# 3_sensors.net
KiCad netlist of a schematic drawn in Altium Designer
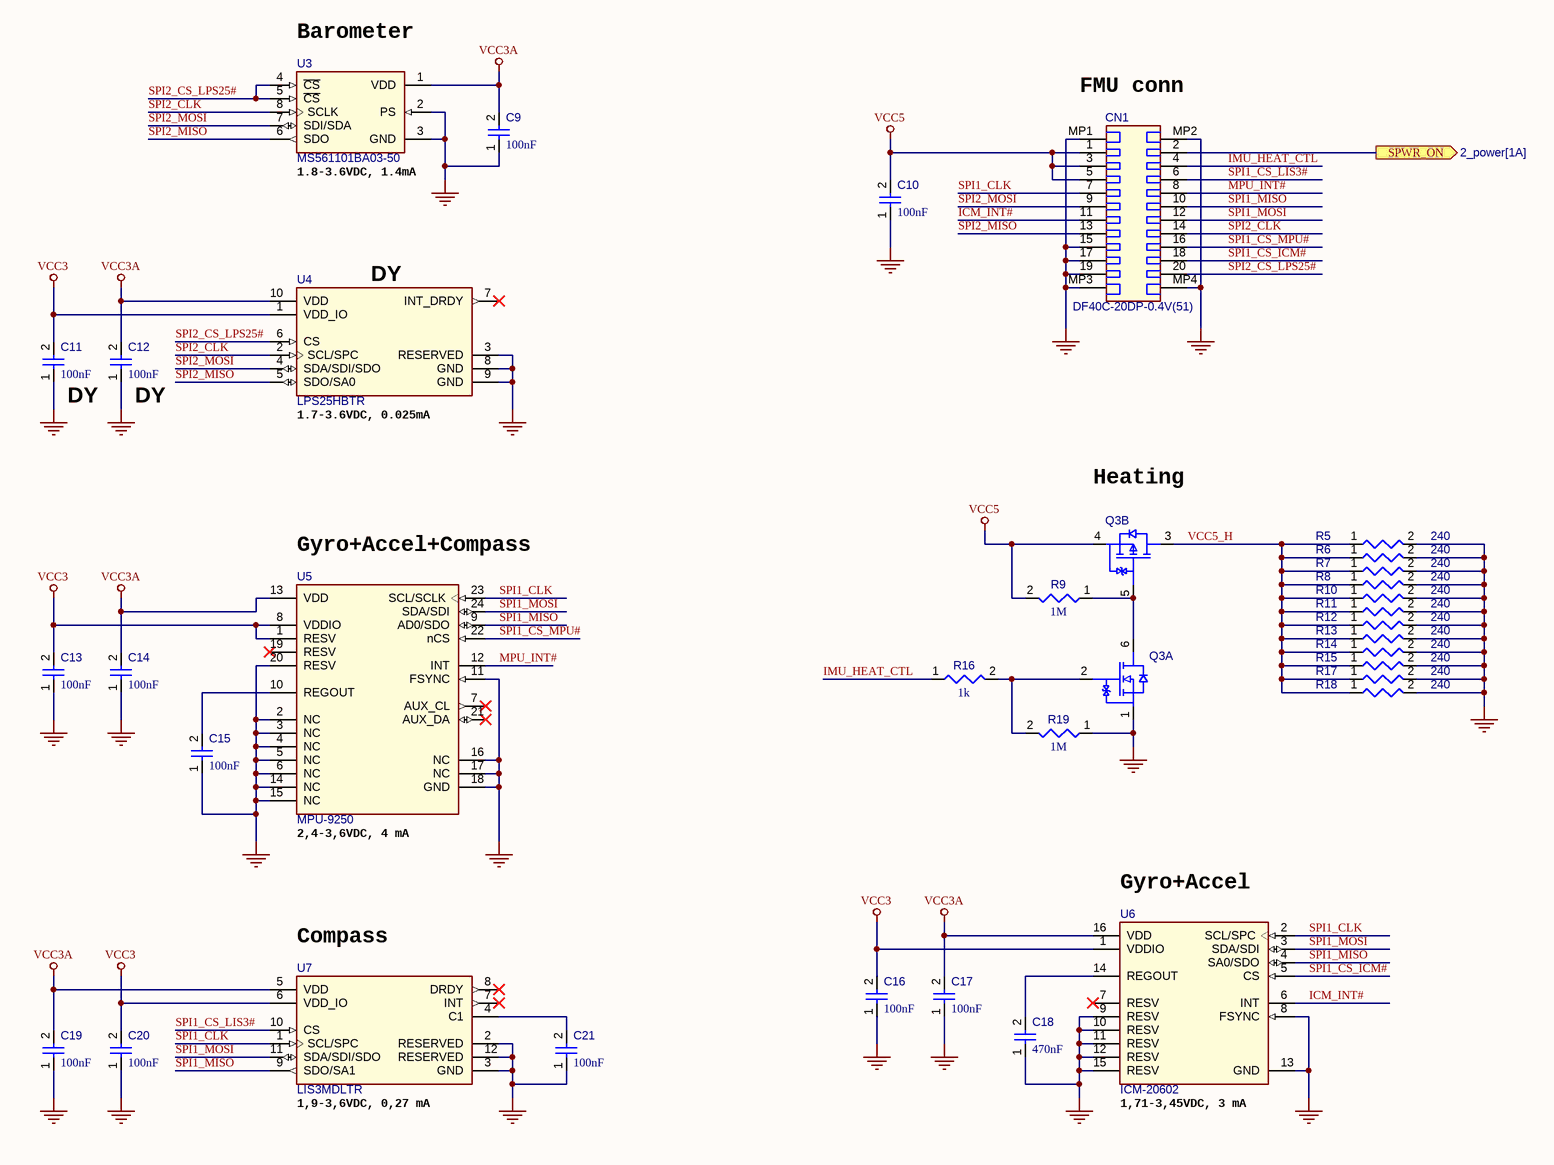
[diagram p0: 3_sensors.SchDoc]

(export (version "E")
  (design (tool "Eeschema 10.0.6"))
  (components
    (comp (ref "C9")
      (value "100nF")
      (footprint "CAPC0402(1005)60_L")
      (description "Chip Capacitor, 100nF +/-20%, 10V, 0402, Thickness 0.6 mm")
      (fields (field (name "TOLERANCE") "20%") (field (name "Comment") "Capacitor 100nF +/-20% 10V 0402"))
      (libsource (lib "SKA- Automa玢o de Engenharias") (part "CAP-NP-2"))
    )
    (comp (ref "C10")
      (value "100nF")
      (footprint "CAPC0402(1005)60_L")
      (description "Chip Capacitor, 100nF +/-20%, 10V, 0402, Thickness 0.6 mm")
      (fields (field (name "TOLERANCE") "20%") (field (name "Comment") "Capacitor 100nF +/-20% 10V 0402"))
      (libsource (lib "SKA- Automa玢o de Engenharias") (part "CAP-NP-2"))
    )
    (comp (ref "C11")
      (value "100nF")
      (footprint "CAPC0402(1005)60_L")
      (description "Chip Capacitor, 100nF +/-20%, 10V, 0402, Thickness 0.6 mm")
      (fields (field (name "TOLERANCE") "20%") (field (name "Comment") "Capacitor 100nF +/-20% 10V 0402"))
      (libsource (lib "SKA- Automa玢o de Engenharias") (part "CAP-NP-2"))
    )
    (comp (ref "C12")
      (value "100nF")
      (footprint "CAPC0402(1005)60_L")
      (description "Chip Capacitor, 100nF +/-20%, 10V, 0402, Thickness 0.6 mm")
      (fields (field (name "TOLERANCE") "20%") (field (name "Comment") "Capacitor 100nF +/-20% 10V 0402"))
      (libsource (lib "SKA- Automa玢o de Engenharias") (part "CAP-NP-2"))
    )
    (comp (ref "C13")
      (value "100nF")
      (footprint "CAPC0402(1005)60_L")
      (description "Chip Capacitor, 100nF +/-20%, 10V, 0402, Thickness 0.6 mm")
      (fields (field (name "TOLERANCE") "20%") (field (name "Comment") "Capacitor 100nF +/-20% 10V 0402"))
      (libsource (lib "SKA- Automa玢o de Engenharias") (part "CAP-NP-2"))
    )
    (comp (ref "C14")
      (value "100nF")
      (footprint "CAPC0402(1005)60_L")
      (description "Chip Capacitor, 100nF +/-20%, 10V, 0402, Thickness 0.6 mm")
      (fields (field (name "TOLERANCE") "20%") (field (name "Comment") "Capacitor 100nF +/-20% 10V 0402"))
      (libsource (lib "SKA- Automa玢o de Engenharias") (part "CAP-NP-2"))
    )
    (comp (ref "C15")
      (value "100nF")
      (footprint "CAPC0402(1005)60_L")
      (description "Chip Capacitor, 100nF +/-20%, 10V, 0402, Thickness 0.6 mm")
      (fields (field (name "TOLERANCE") "20%") (field (name "Comment") "Capacitor 100nF +/-20% 10V 0402"))
      (libsource (lib "SKA- Automa玢o de Engenharias") (part "CAP-NP-2"))
    )
    (comp (ref "C16")
      (value "100nF")
      (footprint "CAPC0402(1005)60_L")
      (description "Chip Capacitor, 100nF +/-20%, 10V, 0402, Thickness 0.6 mm")
      (fields (field (name "TOLERANCE") "20%") (field (name "Comment") "Capacitor 100nF +/-20% 10V 0402"))
      (libsource (lib "SKA- Automa玢o de Engenharias") (part "CAP-NP-2"))
    )
    (comp (ref "C17")
      (value "100nF")
      (footprint "CAPC0402(1005)60_L")
      (description "Chip Capacitor, 100nF +/-20%, 10V, 0402, Thickness 0.6 mm")
      (fields (field (name "TOLERANCE") "20%") (field (name "Comment") "Capacitor 100nF +/-20% 10V 0402"))
      (libsource (lib "SKA- Automa玢o de Engenharias") (part "CAP-NP-2"))
    )
    (comp (ref "C18")
      (value "470nF")
      (footprint "CAPC0402(1005)60_L")
      (description "Chip Capacitor, 470nF +/-40%, 10V, 0402, Thickness 0.6 mm")
      (fields (field (name "TOLERANCE") "20%") (field (name "Comment") "Capacitor 470nF +/-40% 10V 0402"))
      (libsource (lib "SKA- Automa玢o de Engenharias") (part "CAP-NP-2"))
    )
    (comp (ref "C19")
      (value "100nF")
      (footprint "CAPC0402(1005)60_L")
      (description "Chip Capacitor, 100nF +/-20%, 10V, 0402, Thickness 0.6 mm")
      (fields (field (name "TOLERANCE") "20%") (field (name "Comment") "Capacitor 100nF +/-20% 10V 0402"))
      (libsource (lib "SKA- Automa玢o de Engenharias") (part "CAP-NP-2"))
    )
    (comp (ref "C20")
      (value "100nF")
      (footprint "CAPC0402(1005)60_L")
      (description "Chip Capacitor, 100nF +/-20%, 10V, 0402, Thickness 0.6 mm")
      (fields (field (name "TOLERANCE") "20%") (field (name "Comment") "Capacitor 100nF +/-20% 10V 0402"))
      (libsource (lib "SKA- Automa玢o de Engenharias") (part "CAP-NP-2"))
    )
    (comp (ref "C21")
      (value "100nF")
      (footprint "CAPC0402(1005)60_L")
      (description "Chip Capacitor, 100nF +/-20%, 10V, 0402, Thickness 0.6 mm")
      (fields (field (name "TOLERANCE") "20%") (field (name "Comment") "Capacitor 100nF +/-20% 10V 0402"))
      (libsource (lib "SKA- Automa玢o de Engenharias") (part "CAP-NP-2"))
    )
    (comp (ref "CN1")
      (value "DF40C-20DP-0.4V(51)")
      (footprint "HIRO-DF40C-20DP-0.4V(51)_V")
      (description "Plug Connector, 30 V, 0.3 A, -35 to 85 degC, RoHS, Tape and Reel")
      (libsource (lib "<Company> Server") (part "CMP-00102-5"))
    )
    (comp (ref "Q3")
      (value "DMC1030UFDBQ-7")
      (footprint "DMC1030UFDBQ-7-Footprint-1")
      (description "MOSFET N/P-CH 12V 5.1A UDFN2020")
      (libsource (lib "<Company> Server") (part "DMC1030UFDBQ-7"))
    )
    (comp (ref "R5")
      (value "240")
      (footprint "RESC0402(1005)_L")
      (description "Chip Resistor, 240 Ohms, +/-5 %, 63 mW, -55 to 155 degC, 0402")
      (fields (field (name "POWER") "63mW") (field (name "TOLERANCE") "5%"))
      (libsource (lib "<Company> Server") (part "RES-2"))
    )
    (comp (ref "R6")
      (value "240")
      (footprint "RESC0402(1005)_L")
      (description "Chip Resistor, 240 Ohms, +/-5 %, 63 mW, -55 to 155 degC, 0402")
      (fields (field (name "POWER") "63mW") (field (name "TOLERANCE") "5%"))
      (libsource (lib "<Company> Server") (part "RES-2"))
    )
    (comp (ref "R7")
      (value "240")
      (footprint "RESC0402(1005)_L")
      (description "Chip Resistor, 240 Ohms, +/-5 %, 63 mW, -55 to 155 degC, 0402")
      (fields (field (name "POWER") "63mW") (field (name "TOLERANCE") "5%"))
      (libsource (lib "<Company> Server") (part "RES-2"))
    )
    (comp (ref "R8")
      (value "240")
      (footprint "RESC0402(1005)_L")
      (description "Chip Resistor, 240 Ohms, +/-5 %, 63 mW, -55 to 155 degC, 0402")
      (fields (field (name "POWER") "63mW") (field (name "TOLERANCE") "5%"))
      (libsource (lib "<Company> Server") (part "RES-2"))
    )
    (comp (ref "R9")
      (value "1M")
      (footprint "RESC0402(1005)_L")
      (description "Chip Resistor, 1 MOhms, +/-5 %, 63 mW, -55 to 155 degC, 0402")
      (fields (field (name "POWER") "63mW") (field (name "TOLERANCE") "5%"))
      (libsource (lib "SKA- Automa玢o de Engenharias") (part "RES-2"))
    )
    (comp (ref "R10")
      (value "240")
      (footprint "RESC0402(1005)_L")
      (description "Chip Resistor, 240 Ohms, +/-5 %, 63 mW, -55 to 155 degC, 0402")
      (fields (field (name "POWER") "63mW") (field (name "TOLERANCE") "5%"))
      (libsource (lib "<Company> Server") (part "RES-2"))
    )
    (comp (ref "R11")
      (value "240")
      (footprint "RESC0402(1005)_L")
      (description "Chip Resistor, 240 Ohms, +/-5 %, 63 mW, -55 to 155 degC, 0402")
      (fields (field (name "POWER") "63mW") (field (name "TOLERANCE") "5%"))
      (libsource (lib "<Company> Server") (part "RES-2"))
    )
    (comp (ref "R12")
      (value "240")
      (footprint "RESC0402(1005)_L")
      (description "Chip Resistor, 240 Ohms, +/-5 %, 63 mW, -55 to 155 degC, 0402")
      (fields (field (name "POWER") "63mW") (field (name "TOLERANCE") "5%"))
      (libsource (lib "<Company> Server") (part "RES-2"))
    )
    (comp (ref "R13")
      (value "240")
      (footprint "RESC0402(1005)_L")
      (description "Chip Resistor, 240 Ohms, +/-5 %, 63 mW, -55 to 155 degC, 0402")
      (fields (field (name "POWER") "63mW") (field (name "TOLERANCE") "5%"))
      (libsource (lib "<Company> Server") (part "RES-2"))
    )
    (comp (ref "R14")
      (value "240")
      (footprint "RESC0402(1005)_L")
      (description "Chip Resistor, 240 Ohms, +/-5 %, 63 mW, -55 to 155 degC, 0402")
      (fields (field (name "POWER") "63mW") (field (name "TOLERANCE") "5%"))
      (libsource (lib "<Company> Server") (part "RES-2"))
    )
    (comp (ref "R15")
      (value "240")
      (footprint "RESC0402(1005)_L")
      (description "Chip Resistor, 240 Ohms, +/-5 %, 63 mW, -55 to 155 degC, 0402")
      (fields (field (name "POWER") "63mW") (field (name "TOLERANCE") "5%"))
      (libsource (lib "<Company> Server") (part "RES-2"))
    )
    (comp (ref "R16")
      (value "1k")
      (footprint "RESC0402(1005)_L")
      (description "Chip Resistor, 1 kOhms, +/-5 %, 63 mW, -55 to 155 degC, 0402")
      (fields (field (name "POWER") "63mW") (field (name "TOLERANCE") "5%"))
      (libsource (lib "SKA- Automa玢o de Engenharias") (part "RES-2"))
    )
    (comp (ref "R17")
      (value "240")
      (footprint "RESC0402(1005)_L")
      (description "Chip Resistor, 240 Ohms, +/-5 %, 63 mW, -55 to 155 degC, 0402")
      (fields (field (name "POWER") "63mW") (field (name "TOLERANCE") "5%"))
      (libsource (lib "<Company> Server") (part "RES-2"))
    )
    (comp (ref "R18")
      (value "240")
      (footprint "RESC0402(1005)_L")
      (description "Chip Resistor, 240 Ohms, +/-5 %, 63 mW, -55 to 155 degC, 0402")
      (fields (field (name "POWER") "63mW") (field (name "TOLERANCE") "5%"))
      (libsource (lib "<Company> Server") (part "RES-2"))
    )
    (comp (ref "R19")
      (value "1M")
      (footprint "RESC0402(1005)_L")
      (description "Chip Resistor, 1 MOhms, +/-5 %, 63 mW, -55 to 155 degC, 0402")
      (fields (field (name "POWER") "63mW") (field (name "TOLERANCE") "5%"))
      (libsource (lib "SKA- Automa玢o de Engenharias") (part "RES-2"))
    )
    (comp (ref "U3")
      (value "MS561101BA03-50")
      (footprint "TECO-MS561101BA03_V")
      (description "Barometric Pressure Sensor, 1.8 to 3.6 V, -40 to 85 degC, 8-Pin SMD, RoHS, Tape and Reel")
      (libsource (lib "<Company> Server") (part "CMP-00109-8"))
    )
    (comp (ref "U4")
      (value "LPS25HBTR")
      (footprint "STM-LGA-10")
      (description "MEMS Pressure Sensor, 1.7 to 3.6 V, -30 to 105 degC, 10-Pin LGA, RoHS, Tray")
      (libsource (lib "<Company> Server") (part "CMP-00103-10"))
    )
    (comp (ref "U5")
      (value "MPU-9250")
      (footprint "INSE-QFN-24-1700X1540TP_N")
      (description "9-axis MotionTracking device, 2.4 to 3,6 V, -40 to 85 degC, 24-Pin QFN, RoHS, Tape and Reel")
      (libsource (lib "<Company> Server") (part "CMP-00119-6"))
    )
    (comp (ref "U6")
      (value "ICM-20602")
      (footprint "INSE-I62-16")
      (libsource (lib "<Company> Server") (part "CMP-00120-6"))
    )
    (comp (ref "U7")
      (value "LIS3MDLTR")
      (footprint "STM-LGA-12")
      (description "Digital Output Magnetic Sensor, 1.9 to 3.6 V, -40 to 85 degC, 12-Pin LGA, RoHS, Tape and Reel")
      (libsource (lib "<Company> Server") (part "CMP-00084-7"))
    )
  )
  (nets
    (net (code "1") (name "/ICM_INT#") (class "Default")
      (node (ref "CN1") (pin "11") (pinfunction "11_11") (pintype "passive"))
      (node (ref "U6") (pin "6") (pinfunction "INT_6") (pintype "open_collector"))
    )
    (net (code "2") (name "/IMU_HEAT_CTL") (class "Default")
      (node (ref "CN1") (pin "4") (pinfunction "4_4") (pintype "passive"))
      (node (ref "R16") (pin "1") (pinfunction "1_1") (pintype "passive"))
    )
    (net (code "3") (name "/MPU_INT#") (class "Default")
      (node (ref "CN1") (pin "8") (pinfunction "8_8") (pintype "passive"))
      (node (ref "U5") (pin "12") (pinfunction "INT_12") (pintype "tri_state"))
    )
    (net (code "4") (name "/SPI1_CLK") (class "Default")
      (node (ref "CN1") (pin "7") (pinfunction "7_7") (pintype "passive"))
      (node (ref "U5") (pin "23") (pinfunction "SCL/SCLK_23") (pintype "input"))
      (node (ref "U6") (pin "2") (pinfunction "SCL/SPC_2") (pintype "input"))
      (node (ref "U7") (pin "1") (pinfunction "SCL/SPC_1") (pintype "input"))
    )
    (net (code "5") (name "/SPI1_CS_ICM#") (class "Default")
      (node (ref "CN1") (pin "18") (pinfunction "18_18") (pintype "passive"))
      (node (ref "U6") (pin "5") (pinfunction "CS_5") (pintype "input"))
    )
    (net (code "6") (name "/SPI1_CS_LIS3#") (class "Default")
      (node (ref "CN1") (pin "6") (pinfunction "6_6") (pintype "passive"))
      (node (ref "U7") (pin "10") (pinfunction "CS_10") (pintype "input"))
    )
    (net (code "7") (name "/SPI1_CS_MPU#") (class "Default")
      (node (ref "CN1") (pin "16") (pinfunction "16_16") (pintype "passive"))
      (node (ref "U5") (pin "22") (pinfunction "nCS_22") (pintype "input"))
    )
    (net (code "8") (name "/SPI1_MISO") (class "Default")
      (node (ref "CN1") (pin "10") (pinfunction "10_10") (pintype "passive"))
      (node (ref "U5") (pin "9") (pinfunction "AD0/SDO_9") (pintype "bidirectional"))
      (node (ref "U6") (pin "4") (pinfunction "SA0/SDO_4") (pintype "bidirectional"))
      (node (ref "U7") (pin "9") (pinfunction "SDO/SA1_9") (pintype "output"))
    )
    (net (code "9") (name "/SPI1_MOSI") (class "Default")
      (node (ref "CN1") (pin "12") (pinfunction "12_12") (pintype "passive"))
      (node (ref "U5") (pin "24") (pinfunction "SDA/SDI_24") (pintype "bidirectional"))
      (node (ref "U6") (pin "3") (pinfunction "SDA/SDI_3") (pintype "bidirectional"))
      (node (ref "U7") (pin "11") (pinfunction "SDA/SDI/SDO_11") (pintype "bidirectional"))
    )
    (net (code "10") (name "/SPI2_CLK") (class "Default")
      (node (ref "CN1") (pin "14") (pinfunction "14_14") (pintype "passive"))
      (node (ref "U3") (pin "8") (pinfunction "SCLK_8") (pintype "input"))
      (node (ref "U4") (pin "2") (pinfunction "SCL/SPC_2") (pintype "input"))
    )
    (net (code "11") (name "/SPI2_CS_LPS25#") (class "Default")
      (node (ref "CN1") (pin "20") (pinfunction "20_20") (pintype "passive"))
      (node (ref "U3") (pin "4") (pinfunction "~{CS}_4") (pintype "input"))
      (node (ref "U3") (pin "5") (pinfunction "~{CS}_5") (pintype "input"))
      (node (ref "U4") (pin "6") (pinfunction "CS_6") (pintype "input"))
    )
    (net (code "12") (name "/SPI2_MISO") (class "Default")
      (node (ref "CN1") (pin "13") (pinfunction "13_13") (pintype "passive"))
      (node (ref "U3") (pin "6") (pinfunction "SDO_6") (pintype "output"))
      (node (ref "U4") (pin "5") (pinfunction "SDO/SA0_5") (pintype "bidirectional"))
    )
    (net (code "13") (name "/SPI2_MOSI") (class "Default")
      (node (ref "CN1") (pin "9") (pinfunction "9_9") (pintype "passive"))
      (node (ref "U3") (pin "7") (pinfunction "SDI/SDA_7") (pintype "bidirectional"))
      (node (ref "U4") (pin "4") (pinfunction "SDA/SDI/SDO_4") (pintype "bidirectional"))
    )
    (net (code "14") (name "/SPWR_ON") (class "Default")
      (node (ref "CN1") (pin "2") (pinfunction "2_2") (pintype "passive"))
    )
    (net (code "15") (name "/VCC5_H") (class "Default")
      (node (ref "Q3") (pin "3") (pinfunction "D2_3") (pintype "passive"))
      (node (ref "R10") (pin "1") (pinfunction "1_1") (pintype "passive"))
      (node (ref "R11") (pin "1") (pinfunction "1_1") (pintype "passive"))
      (node (ref "R12") (pin "1") (pinfunction "1_1") (pintype "passive"))
      (node (ref "R13") (pin "1") (pinfunction "1_1") (pintype "passive"))
      (node (ref "R14") (pin "1") (pinfunction "1_1") (pintype "passive"))
      (node (ref "R15") (pin "1") (pinfunction "1_1") (pintype "passive"))
      (node (ref "R17") (pin "1") (pinfunction "1_1") (pintype "passive"))
      (node (ref "R18") (pin "1") (pinfunction "1_1") (pintype "passive"))
      (node (ref "R5") (pin "1") (pinfunction "1_1") (pintype "passive"))
      (node (ref "R6") (pin "1") (pinfunction "1_1") (pintype "passive"))
      (node (ref "R7") (pin "1") (pinfunction "1_1") (pintype "passive"))
      (node (ref "R8") (pin "1") (pinfunction "1_1") (pintype "passive"))
    )
    (net (code "16") (name "GND") (class "Default")
      (node (ref "C10") (pin "1") (pinfunction "1_1") (pintype "passive"))
      (node (ref "C11") (pin "1") (pinfunction "1_1") (pintype "passive"))
      (node (ref "C12") (pin "1") (pinfunction "1_1") (pintype "passive"))
      (node (ref "C13") (pin "1") (pinfunction "1_1") (pintype "passive"))
      (node (ref "C14") (pin "1") (pinfunction "1_1") (pintype "passive"))
      (node (ref "C15") (pin "1") (pinfunction "1_1") (pintype "passive"))
      (node (ref "C16") (pin "1") (pinfunction "1_1") (pintype "passive"))
      (node (ref "C17") (pin "1") (pinfunction "1_1") (pintype "passive"))
      (node (ref "C18") (pin "1") (pinfunction "1_1") (pintype "passive"))
      (node (ref "C19") (pin "1") (pinfunction "1_1") (pintype "passive"))
      (node (ref "C20") (pin "1") (pinfunction "1_1") (pintype "passive"))
      (node (ref "C21") (pin "1") (pinfunction "1_1") (pintype "passive"))
      (node (ref "C9") (pin "1") (pinfunction "1_1") (pintype "passive"))
      (node (ref "CN1") (pin "15") (pinfunction "15_15") (pintype "passive"))
      (node (ref "CN1") (pin "17") (pinfunction "17_17") (pintype "passive"))
      (node (ref "CN1") (pin "19") (pinfunction "19_19") (pintype "passive"))
      (node (ref "CN1") (pin "MP1") (pinfunction "MP_MP1") (pintype "passive"))
      (node (ref "CN1") (pin "MP2") (pinfunction "MP_MP2") (pintype "passive"))
      (node (ref "CN1") (pin "MP3") (pinfunction "MP_MP3") (pintype "passive"))
      (node (ref "CN1") (pin "MP4") (pinfunction "MP_MP4") (pintype "passive"))
      (node (ref "Q3") (pin "1") (pinfunction "S1_1") (pintype "passive"))
      (node (ref "R10") (pin "2") (pinfunction "2_2") (pintype "passive"))
      (node (ref "R11") (pin "2") (pinfunction "2_2") (pintype "passive"))
      (node (ref "R12") (pin "2") (pinfunction "2_2") (pintype "passive"))
      (node (ref "R13") (pin "2") (pinfunction "2_2") (pintype "passive"))
      (node (ref "R14") (pin "2") (pinfunction "2_2") (pintype "passive"))
      (node (ref "R15") (pin "2") (pinfunction "2_2") (pintype "passive"))
      (node (ref "R17") (pin "2") (pinfunction "2_2") (pintype "passive"))
      (node (ref "R18") (pin "2") (pinfunction "2_2") (pintype "passive"))
      (node (ref "R19") (pin "1") (pinfunction "1_1") (pintype "passive"))
      (node (ref "R5") (pin "2") (pinfunction "2_2") (pintype "passive"))
      (node (ref "R6") (pin "2") (pinfunction "2_2") (pintype "passive"))
      (node (ref "R7") (pin "2") (pinfunction "2_2") (pintype "passive"))
      (node (ref "R8") (pin "2") (pinfunction "2_2") (pintype "passive"))
      (node (ref "U3") (pin "2") (pinfunction "PS_2") (pintype "input"))
      (node (ref "U3") (pin "3") (pinfunction "GND_3") (pintype "power_in"))
      (node (ref "U4") (pin "3") (pinfunction "RESERVED_3") (pintype "passive"))
      (node (ref "U4") (pin "8") (pinfunction "GND_8") (pintype "power_in"))
      (node (ref "U4") (pin "9") (pinfunction "GND_9") (pintype "power_in"))
      (node (ref "U5") (pin "11") (pinfunction "FSYNC_11") (pintype "input"))
      (node (ref "U5") (pin "14") (pinfunction "NC_14") (pintype "passive"))
      (node (ref "U5") (pin "15") (pinfunction "NC_15") (pintype "passive"))
      (node (ref "U5") (pin "16") (pinfunction "NC_16") (pintype "passive"))
      (node (ref "U5") (pin "17") (pinfunction "NC_17") (pintype "passive"))
      (node (ref "U5") (pin "18") (pinfunction "GND_18") (pintype "power_in"))
      (node (ref "U5") (pin "2") (pinfunction "NC_2") (pintype "passive"))
      (node (ref "U5") (pin "20") (pinfunction "RESV_20") (pintype "power_in"))
      (node (ref "U5") (pin "3") (pinfunction "NC_3") (pintype "passive"))
      (node (ref "U5") (pin "4") (pinfunction "NC_4") (pintype "passive"))
      (node (ref "U5") (pin "5") (pinfunction "NC_5") (pintype "passive"))
      (node (ref "U5") (pin "6") (pinfunction "NC_6") (pintype "passive"))
      (node (ref "U6") (pin "10") (pinfunction "RESV_10") (pintype "passive"))
      (node (ref "U6") (pin "11") (pinfunction "RESV_11") (pintype "passive"))
      (node (ref "U6") (pin "12") (pinfunction "RESV_12") (pintype "passive"))
      (node (ref "U6") (pin "13") (pinfunction "GND_13") (pintype "power_in"))
      (node (ref "U6") (pin "15") (pinfunction "RESV_15") (pintype "passive"))
      (node (ref "U6") (pin "8") (pinfunction "FSYNC_8") (pintype "input"))
      (node (ref "U6") (pin "9") (pinfunction "RESV_9") (pintype "passive"))
      (node (ref "U7") (pin "12") (pinfunction "RESERVED_12") (pintype "passive"))
      (node (ref "U7") (pin "2") (pinfunction "RESERVED_2") (pintype "passive"))
      (node (ref "U7") (pin "3") (pinfunction "GND_3") (pintype "power_in"))
    )
    (net (code "17") (name "Net-(Q3A-D1)") (class "Default")
      (node (ref "Q3") (pin "5") (pinfunction "G2_5") (pintype "passive"))
      (node (ref "Q3") (pin "6") (pinfunction "D1_6") (pintype "passive"))
      (node (ref "R9") (pin "1") (pinfunction "1_1") (pintype "passive"))
    )
    (net (code "18") (name "Net-(Q3A-G1)") (class "Default")
      (node (ref "Q3") (pin "2") (pinfunction "G1_2") (pintype "passive"))
      (node (ref "R16") (pin "2") (pinfunction "2_2") (pintype "passive"))
      (node (ref "R19") (pin "2") (pinfunction "2_2") (pintype "passive"))
    )
    (net (code "19") (name "Net-(U5-REGOUT)") (class "Default")
      (node (ref "C15") (pin "2") (pinfunction "2_2") (pintype "passive"))
      (node (ref "U5") (pin "10") (pinfunction "REGOUT_10") (pintype "passive"))
    )
    (net (code "20") (name "Net-(U6-REGOUT)") (class "Default")
      (node (ref "C18") (pin "2") (pinfunction "2_2") (pintype "passive"))
      (node (ref "U6") (pin "14") (pinfunction "REGOUT_14") (pintype "passive"))
    )
    (net (code "21") (name "Net-(U7-C1)") (class "Default")
      (node (ref "C21") (pin "2") (pinfunction "2_2") (pintype "passive"))
      (node (ref "U7") (pin "4") (pinfunction "C1_4") (pintype "passive"))
    )
    (net (code "22") (name "VCC3") (class "Default")
      (node (ref "C11") (pin "2") (pinfunction "2_2") (pintype "passive"))
      (node (ref "C13") (pin "2") (pinfunction "2_2") (pintype "passive"))
      (node (ref "C16") (pin "2") (pinfunction "2_2") (pintype "passive"))
      (node (ref "C20") (pin "2") (pinfunction "2_2") (pintype "passive"))
      (node (ref "U4") (pin "1") (pinfunction "VDD_IO_1") (pintype "power_in"))
      (node (ref "U5") (pin "1") (pinfunction "RESV_1") (pintype "power_in"))
      (node (ref "U5") (pin "8") (pinfunction "VDDIO_8") (pintype "power_in"))
      (node (ref "U6") (pin "1") (pinfunction "VDDIO_1") (pintype "power_in"))
      (node (ref "U7") (pin "6") (pinfunction "VDD_IO_6") (pintype "power_in"))
    )
    (net (code "23") (name "VCC3A") (class "Default")
      (node (ref "C12") (pin "2") (pinfunction "2_2") (pintype "passive"))
      (node (ref "C14") (pin "2") (pinfunction "2_2") (pintype "passive"))
      (node (ref "C17") (pin "2") (pinfunction "2_2") (pintype "passive"))
      (node (ref "C19") (pin "2") (pinfunction "2_2") (pintype "passive"))
      (node (ref "C9") (pin "2") (pinfunction "2_2") (pintype "passive"))
      (node (ref "U3") (pin "1") (pinfunction "VDD_1") (pintype "power_in"))
      (node (ref "U4") (pin "10") (pinfunction "VDD_10") (pintype "power_in"))
      (node (ref "U5") (pin "13") (pinfunction "VDD_13") (pintype "power_in"))
      (node (ref "U6") (pin "16") (pinfunction "VDD_16") (pintype "power_in"))
      (node (ref "U7") (pin "5") (pinfunction "VDD_5") (pintype "power_in"))
    )
    (net (code "24") (name "VCC5") (class "Default")
      (node (ref "C10") (pin "2") (pinfunction "2_2") (pintype "passive"))
      (node (ref "CN1") (pin "1") (pinfunction "1_1") (pintype "passive"))
      (node (ref "CN1") (pin "3") (pinfunction "3_3") (pintype "passive"))
      (node (ref "CN1") (pin "5") (pinfunction "5_5") (pintype "passive"))
      (node (ref "Q3") (pin "4") (pinfunction "S2_4") (pintype "passive"))
      (node (ref "R9") (pin "2") (pinfunction "2_2") (pintype "passive"))
    )
    (net (code "25") (name "unconnected-(U4-INT_DRDY-Pad7)") (class "Default")
      (node (ref "U4") (pin "7") (pinfunction "INT_DRDY_7") (pintype "output+no_connect"))
    )
    (net (code "26") (name "unconnected-(U5-AUX_CL-Pad7)") (class "Default")
      (node (ref "U5") (pin "7") (pinfunction "AUX_CL_7") (pintype "output+no_connect"))
    )
    (net (code "27") (name "unconnected-(U5-AUX_DA-Pad21)") (class "Default")
      (node (ref "U5") (pin "21") (pinfunction "AUX_DA_21") (pintype "bidirectional+no_connect"))
    )
    (net (code "28") (name "unconnected-(U5-RESV-Pad19)") (class "Default")
      (node (ref "U5") (pin "19") (pinfunction "RESV_19") (pintype "passive+no_connect"))
    )
    (net (code "29") (name "unconnected-(U6-RESV-Pad7)") (class "Default")
      (node (ref "U6") (pin "7") (pinfunction "RESV_7") (pintype "passive+no_connect"))
    )
    (net (code "30") (name "unconnected-(U7-DRDY-Pad8)") (class "Default")
      (node (ref "U7") (pin "8") (pinfunction "DRDY_8") (pintype "output+no_connect"))
    )
    (net (code "31") (name "unconnected-(U7-INT-Pad7)") (class "Default")
      (node (ref "U7") (pin "7") (pinfunction "INT_7") (pintype "output+no_connect"))
    )
  )
)
